# cpu_board.net
KiCad netlist of a schematic drawn in EAGLE
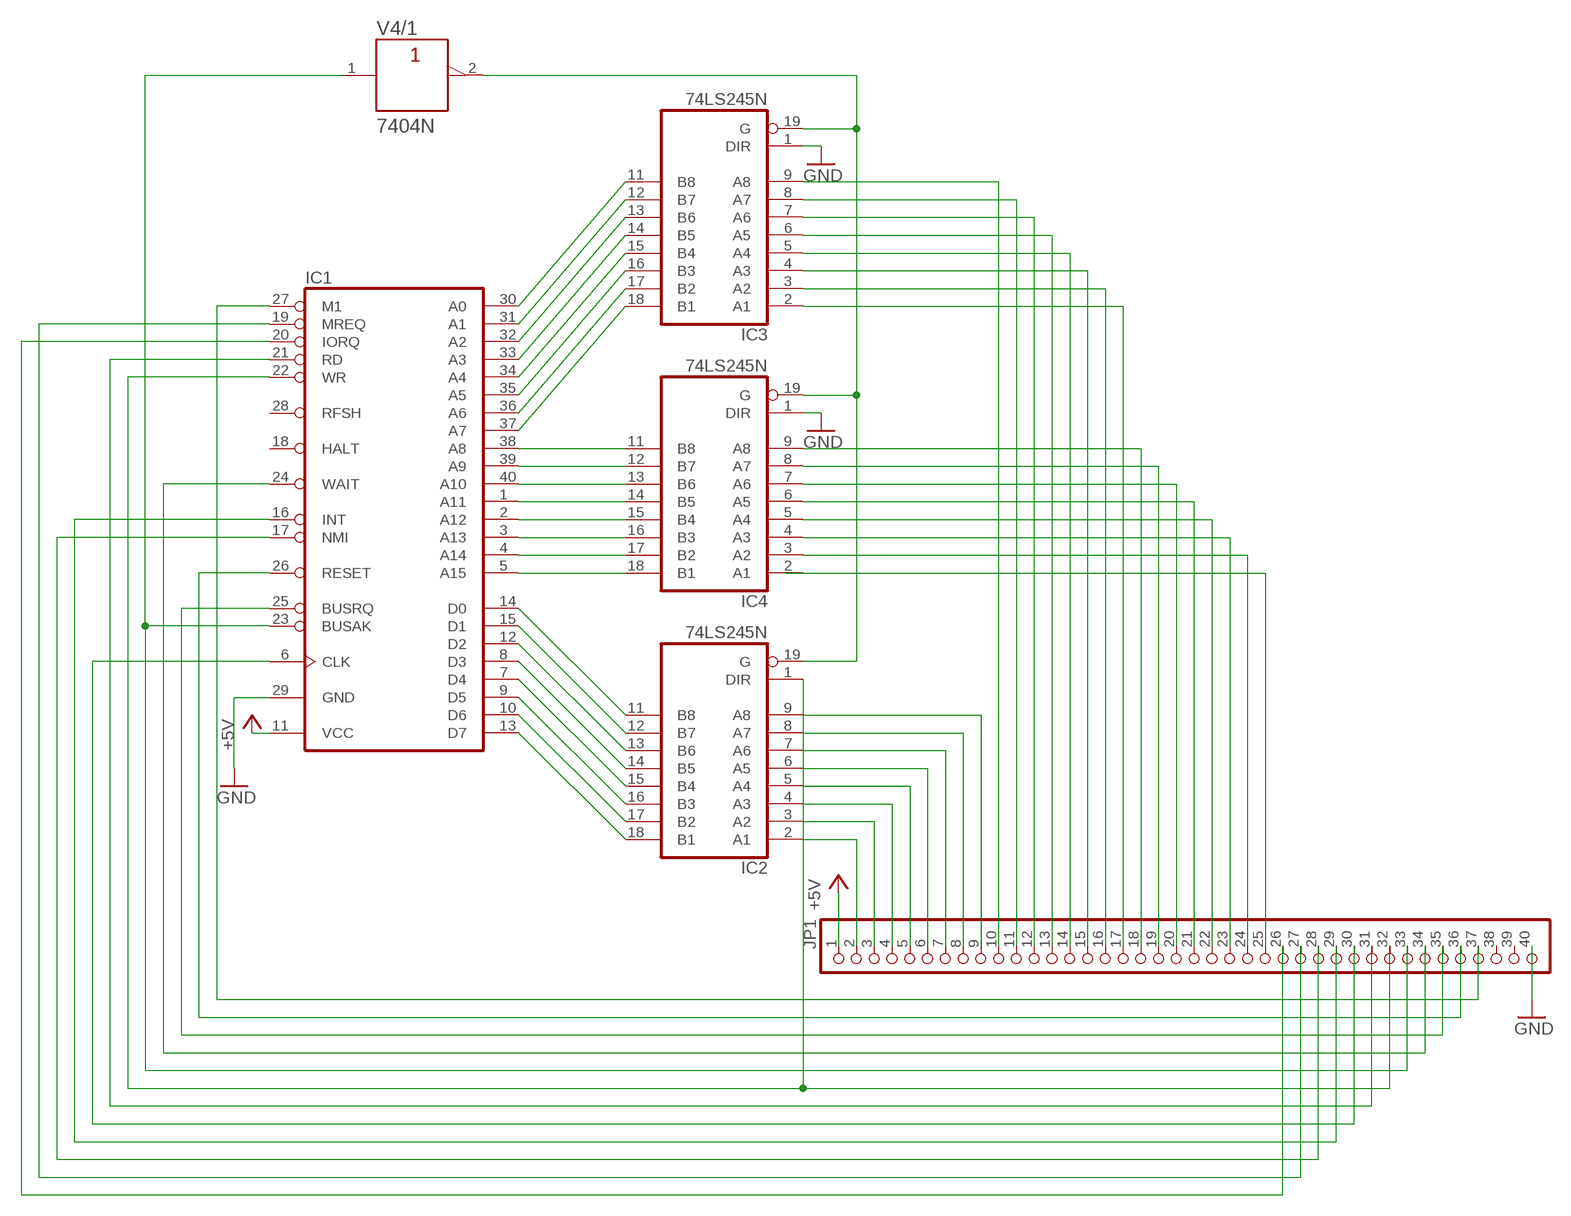
[diagram p0: schematic, sheet 1]

(export (version "E")
  (design (tool "Eeschema 10.0.6"))
  (components
    (comp (ref "IC1")
      (value "Z80CPU")
      (footprint "eagle-import:DIL40")
      (libsource (lib "eagle-import") (part "Z80CPU"))
    )
    (comp (ref "IC2")
      (value "74LS245N")
      (footprint "eagle-import:DIL20")
      (libsource (lib "eagle-import") (part "74245NLS"))
    )
    (comp (ref "IC3")
      (value "74LS245N")
      (footprint "eagle-import:DIL20")
      (libsource (lib "eagle-import") (part "74245NLS"))
    )
    (comp (ref "IC4")
      (value "74LS245N")
      (footprint "eagle-import:DIL20")
      (libsource (lib "eagle-import") (part "74245NLS"))
    )
    (comp (ref "JP1")
      (value "PINHD-1X40")
      (footprint "eagle-import:1X40")
      (libsource (lib "eagle-import") (part "PINHD-1X40"))
    )
    (comp (ref "V4")
      (value "7404N")
      (footprint "eagle-import:DIL14")
      (libsource (lib "eagle-import") (part "7404N"))
    )
  )
  (nets
    (net (code "1") (name "+5V") (class "Default")
      (node (ref "IC1") (pin "11") (pinfunction "VCC_11") (pintype "power_in"))
      (node (ref "JP1") (pin "1") (pinfunction "1_1") (pintype "passive"))
    )
    (net (code "2") (name "GND") (class "Default")
      (node (ref "IC1") (pin "29") (pinfunction "GND_29") (pintype "power_in"))
      (node (ref "IC3") (pin "1") (pinfunction "DIR_1") (pintype "input"))
      (node (ref "IC4") (pin "1") (pinfunction "DIR_1") (pintype "input"))
      (node (ref "JP1") (pin "40") (pinfunction "40_40") (pintype "passive"))
    )
    (net (code "3") (name "Net-(IC1-A0)") (class "Default")
      (node (ref "IC1") (pin "30") (pinfunction "A0_30") (pintype "output"))
      (node (ref "IC3") (pin "11") (pinfunction "B8_11") (pintype "bidirectional"))
    )
    (net (code "4") (name "Net-(IC1-A1)") (class "Default")
      (node (ref "IC1") (pin "31") (pinfunction "A1_31") (pintype "output"))
      (node (ref "IC3") (pin "12") (pinfunction "B7_12") (pintype "bidirectional"))
    )
    (net (code "5") (name "Net-(IC1-A2)") (class "Default")
      (node (ref "IC1") (pin "32") (pinfunction "A2_32") (pintype "output"))
      (node (ref "IC3") (pin "13") (pinfunction "B6_13") (pintype "bidirectional"))
    )
    (net (code "6") (name "Net-(IC1-A3)") (class "Default")
      (node (ref "IC1") (pin "33") (pinfunction "A3_33") (pintype "output"))
      (node (ref "IC3") (pin "14") (pinfunction "B5_14") (pintype "bidirectional"))
    )
    (net (code "7") (name "Net-(IC1-A4)") (class "Default")
      (node (ref "IC1") (pin "34") (pinfunction "A4_34") (pintype "output"))
      (node (ref "IC3") (pin "15") (pinfunction "B4_15") (pintype "bidirectional"))
    )
    (net (code "8") (name "Net-(IC1-A5)") (class "Default")
      (node (ref "IC1") (pin "35") (pinfunction "A5_35") (pintype "output"))
      (node (ref "IC3") (pin "16") (pinfunction "B3_16") (pintype "bidirectional"))
    )
    (net (code "9") (name "Net-(IC1-A6)") (class "Default")
      (node (ref "IC1") (pin "36") (pinfunction "A6_36") (pintype "output"))
      (node (ref "IC3") (pin "17") (pinfunction "B2_17") (pintype "bidirectional"))
    )
    (net (code "10") (name "Net-(IC1-A7)") (class "Default")
      (node (ref "IC1") (pin "37") (pinfunction "A7_37") (pintype "output"))
      (node (ref "IC3") (pin "18") (pinfunction "B1_18") (pintype "bidirectional"))
    )
    (net (code "11") (name "Net-(IC1-A8)") (class "Default")
      (node (ref "IC1") (pin "38") (pinfunction "A8_38") (pintype "output"))
      (node (ref "IC4") (pin "11") (pinfunction "B8_11") (pintype "bidirectional"))
    )
    (net (code "12") (name "Net-(IC1-A9)") (class "Default")
      (node (ref "IC1") (pin "39") (pinfunction "A9_39") (pintype "output"))
      (node (ref "IC4") (pin "12") (pinfunction "B7_12") (pintype "bidirectional"))
    )
    (net (code "13") (name "Net-(IC1-A10)") (class "Default")
      (node (ref "IC1") (pin "40") (pinfunction "A10_40") (pintype "output"))
      (node (ref "IC4") (pin "13") (pinfunction "B6_13") (pintype "bidirectional"))
    )
    (net (code "14") (name "Net-(IC1-A11)") (class "Default")
      (node (ref "IC1") (pin "1") (pinfunction "A11_1") (pintype "output"))
      (node (ref "IC4") (pin "14") (pinfunction "B5_14") (pintype "bidirectional"))
    )
    (net (code "15") (name "Net-(IC1-A12)") (class "Default")
      (node (ref "IC1") (pin "2") (pinfunction "A12_2") (pintype "output"))
      (node (ref "IC4") (pin "15") (pinfunction "B4_15") (pintype "bidirectional"))
    )
    (net (code "16") (name "Net-(IC1-A13)") (class "Default")
      (node (ref "IC1") (pin "3") (pinfunction "A13_3") (pintype "output"))
      (node (ref "IC4") (pin "16") (pinfunction "B3_16") (pintype "bidirectional"))
    )
    (net (code "17") (name "Net-(IC1-A14)") (class "Default")
      (node (ref "IC1") (pin "4") (pinfunction "A14_4") (pintype "output"))
      (node (ref "IC4") (pin "17") (pinfunction "B2_17") (pintype "bidirectional"))
    )
    (net (code "18") (name "Net-(IC1-A15)") (class "Default")
      (node (ref "IC1") (pin "5") (pinfunction "A15_5") (pintype "output"))
      (node (ref "IC4") (pin "18") (pinfunction "B1_18") (pintype "bidirectional"))
    )
    (net (code "19") (name "Net-(IC1-BUSAK)") (class "Default")
      (node (ref "IC1") (pin "23") (pinfunction "BUSAK_23") (pintype "output"))
      (node (ref "JP1") (pin "33") (pinfunction "33_33") (pintype "passive"))
      (node (ref "V4") (pin "1") (pinfunction "A_1") (pintype "input"))
    )
    (net (code "20") (name "Net-(IC1-BUSRQ)") (class "Default")
      (node (ref "IC1") (pin "25") (pinfunction "BUSRQ_25") (pintype "input"))
      (node (ref "JP1") (pin "35") (pinfunction "35_35") (pintype "passive"))
    )
    (net (code "21") (name "Net-(IC1-CLK)") (class "Default")
      (node (ref "IC1") (pin "6") (pinfunction "CLK_6") (pintype "input"))
      (node (ref "JP1") (pin "30") (pinfunction "30_30") (pintype "passive"))
    )
    (net (code "22") (name "Net-(IC1-D0)") (class "Default")
      (node (ref "IC1") (pin "14") (pinfunction "D0_14") (pintype "bidirectional"))
      (node (ref "IC2") (pin "11") (pinfunction "B8_11") (pintype "bidirectional"))
    )
    (net (code "23") (name "Net-(IC1-D1)") (class "Default")
      (node (ref "IC1") (pin "15") (pinfunction "D1_15") (pintype "bidirectional"))
      (node (ref "IC2") (pin "12") (pinfunction "B7_12") (pintype "bidirectional"))
    )
    (net (code "24") (name "Net-(IC1-D2)") (class "Default")
      (node (ref "IC1") (pin "12") (pinfunction "D2_12") (pintype "bidirectional"))
      (node (ref "IC2") (pin "13") (pinfunction "B6_13") (pintype "bidirectional"))
    )
    (net (code "25") (name "Net-(IC1-D3)") (class "Default")
      (node (ref "IC1") (pin "8") (pinfunction "D3_8") (pintype "bidirectional"))
      (node (ref "IC2") (pin "14") (pinfunction "B5_14") (pintype "bidirectional"))
    )
    (net (code "26") (name "Net-(IC1-D4)") (class "Default")
      (node (ref "IC1") (pin "7") (pinfunction "D4_7") (pintype "bidirectional"))
      (node (ref "IC2") (pin "15") (pinfunction "B4_15") (pintype "bidirectional"))
    )
    (net (code "27") (name "Net-(IC1-D5)") (class "Default")
      (node (ref "IC1") (pin "9") (pinfunction "D5_9") (pintype "bidirectional"))
      (node (ref "IC2") (pin "16") (pinfunction "B3_16") (pintype "bidirectional"))
    )
    (net (code "28") (name "Net-(IC1-D6)") (class "Default")
      (node (ref "IC1") (pin "10") (pinfunction "D6_10") (pintype "bidirectional"))
      (node (ref "IC2") (pin "17") (pinfunction "B2_17") (pintype "bidirectional"))
    )
    (net (code "29") (name "Net-(IC1-D7)") (class "Default")
      (node (ref "IC1") (pin "13") (pinfunction "D7_13") (pintype "bidirectional"))
      (node (ref "IC2") (pin "18") (pinfunction "B1_18") (pintype "bidirectional"))
    )
    (net (code "30") (name "Net-(IC1-INT)") (class "Default")
      (node (ref "IC1") (pin "16") (pinfunction "INT_16") (pintype "input"))
      (node (ref "JP1") (pin "29") (pinfunction "29_29") (pintype "passive"))
    )
    (net (code "31") (name "Net-(IC1-IORQ)") (class "Default")
      (node (ref "IC1") (pin "20") (pinfunction "IORQ_20") (pintype "output"))
      (node (ref "JP1") (pin "26") (pinfunction "26_26") (pintype "passive"))
    )
    (net (code "32") (name "Net-(IC1-M1)") (class "Default")
      (node (ref "IC1") (pin "27") (pinfunction "M1_27") (pintype "output"))
      (node (ref "JP1") (pin "37") (pinfunction "37_37") (pintype "passive"))
    )
    (net (code "33") (name "Net-(IC1-MREQ)") (class "Default")
      (node (ref "IC1") (pin "19") (pinfunction "MREQ_19") (pintype "output"))
      (node (ref "JP1") (pin "27") (pinfunction "27_27") (pintype "passive"))
    )
    (net (code "34") (name "Net-(IC1-NMI)") (class "Default")
      (node (ref "IC1") (pin "17") (pinfunction "NMI_17") (pintype "input"))
      (node (ref "JP1") (pin "28") (pinfunction "28_28") (pintype "passive"))
    )
    (net (code "35") (name "Net-(IC1-RD)") (class "Default")
      (node (ref "IC1") (pin "21") (pinfunction "RD_21") (pintype "output"))
      (node (ref "JP1") (pin "31") (pinfunction "31_31") (pintype "passive"))
    )
    (net (code "36") (name "Net-(IC1-RESET)") (class "Default")
      (node (ref "IC1") (pin "26") (pinfunction "RESET_26") (pintype "input"))
      (node (ref "JP1") (pin "36") (pinfunction "36_36") (pintype "passive"))
    )
    (net (code "37") (name "Net-(IC1-WAIT)") (class "Default")
      (node (ref "IC1") (pin "24") (pinfunction "WAIT_24") (pintype "input"))
      (node (ref "JP1") (pin "34") (pinfunction "34_34") (pintype "passive"))
    )
    (net (code "38") (name "Net-(IC1-WR)") (class "Default")
      (node (ref "IC1") (pin "22") (pinfunction "WR_22") (pintype "output"))
      (node (ref "IC2") (pin "1") (pinfunction "DIR_1") (pintype "input"))
      (node (ref "JP1") (pin "32") (pinfunction "32_32") (pintype "passive"))
    )
    (net (code "39") (name "Net-(IC2A-A1)") (class "Default")
      (node (ref "IC2") (pin "2") (pinfunction "A1_2") (pintype "bidirectional"))
      (node (ref "JP1") (pin "2") (pinfunction "2_2") (pintype "passive"))
    )
    (net (code "40") (name "Net-(IC2A-A2)") (class "Default")
      (node (ref "IC2") (pin "3") (pinfunction "A2_3") (pintype "bidirectional"))
      (node (ref "JP1") (pin "3") (pinfunction "3_3") (pintype "passive"))
    )
    (net (code "41") (name "Net-(IC2A-A3)") (class "Default")
      (node (ref "IC2") (pin "4") (pinfunction "A3_4") (pintype "bidirectional"))
      (node (ref "JP1") (pin "4") (pinfunction "4_4") (pintype "passive"))
    )
    (net (code "42") (name "Net-(IC2A-A4)") (class "Default")
      (node (ref "IC2") (pin "5") (pinfunction "A4_5") (pintype "bidirectional"))
      (node (ref "JP1") (pin "5") (pinfunction "5_5") (pintype "passive"))
    )
    (net (code "43") (name "Net-(IC2A-A5)") (class "Default")
      (node (ref "IC2") (pin "6") (pinfunction "A5_6") (pintype "bidirectional"))
      (node (ref "JP1") (pin "6") (pinfunction "6_6") (pintype "passive"))
    )
    (net (code "44") (name "Net-(IC2A-A6)") (class "Default")
      (node (ref "IC2") (pin "7") (pinfunction "A6_7") (pintype "bidirectional"))
      (node (ref "JP1") (pin "7") (pinfunction "7_7") (pintype "passive"))
    )
    (net (code "45") (name "Net-(IC2A-A7)") (class "Default")
      (node (ref "IC2") (pin "8") (pinfunction "A7_8") (pintype "bidirectional"))
      (node (ref "JP1") (pin "8") (pinfunction "8_8") (pintype "passive"))
    )
    (net (code "46") (name "Net-(IC2A-A8)") (class "Default")
      (node (ref "IC2") (pin "9") (pinfunction "A8_9") (pintype "bidirectional"))
      (node (ref "JP1") (pin "9") (pinfunction "9_9") (pintype "passive"))
    )
    (net (code "47") (name "Net-(IC2A-G)") (class "Default")
      (node (ref "IC2") (pin "19") (pinfunction "G_19") (pintype "input"))
      (node (ref "IC3") (pin "19") (pinfunction "G_19") (pintype "input"))
      (node (ref "IC4") (pin "19") (pinfunction "G_19") (pintype "input"))
      (node (ref "V4") (pin "2") (pinfunction "Y_2") (pintype "output"))
    )
    (net (code "48") (name "Net-(IC3A-A1)") (class "Default")
      (node (ref "IC3") (pin "2") (pinfunction "A1_2") (pintype "bidirectional"))
      (node (ref "JP1") (pin "17") (pinfunction "17_17") (pintype "passive"))
    )
    (net (code "49") (name "Net-(IC3A-A2)") (class "Default")
      (node (ref "IC3") (pin "3") (pinfunction "A2_3") (pintype "bidirectional"))
      (node (ref "JP1") (pin "16") (pinfunction "16_16") (pintype "passive"))
    )
    (net (code "50") (name "Net-(IC3A-A3)") (class "Default")
      (node (ref "IC3") (pin "4") (pinfunction "A3_4") (pintype "bidirectional"))
      (node (ref "JP1") (pin "15") (pinfunction "15_15") (pintype "passive"))
    )
    (net (code "51") (name "Net-(IC3A-A4)") (class "Default")
      (node (ref "IC3") (pin "5") (pinfunction "A4_5") (pintype "bidirectional"))
      (node (ref "JP1") (pin "14") (pinfunction "14_14") (pintype "passive"))
    )
    (net (code "52") (name "Net-(IC3A-A5)") (class "Default")
      (node (ref "IC3") (pin "6") (pinfunction "A5_6") (pintype "bidirectional"))
      (node (ref "JP1") (pin "13") (pinfunction "13_13") (pintype "passive"))
    )
    (net (code "53") (name "Net-(IC3A-A6)") (class "Default")
      (node (ref "IC3") (pin "7") (pinfunction "A6_7") (pintype "bidirectional"))
      (node (ref "JP1") (pin "12") (pinfunction "12_12") (pintype "passive"))
    )
    (net (code "54") (name "Net-(IC3A-A7)") (class "Default")
      (node (ref "IC3") (pin "8") (pinfunction "A7_8") (pintype "bidirectional"))
      (node (ref "JP1") (pin "11") (pinfunction "11_11") (pintype "passive"))
    )
    (net (code "55") (name "Net-(IC3A-A8)") (class "Default")
      (node (ref "IC3") (pin "9") (pinfunction "A8_9") (pintype "bidirectional"))
      (node (ref "JP1") (pin "10") (pinfunction "10_10") (pintype "passive"))
    )
    (net (code "56") (name "Net-(IC4A-A2)") (class "Default")
      (node (ref "IC4") (pin "3") (pinfunction "A2_3") (pintype "bidirectional"))
      (node (ref "JP1") (pin "24") (pinfunction "24_24") (pintype "passive"))
    )
    (net (code "57") (name "Net-(IC4A-A3)") (class "Default")
      (node (ref "IC4") (pin "4") (pinfunction "A3_4") (pintype "bidirectional"))
      (node (ref "JP1") (pin "23") (pinfunction "23_23") (pintype "passive"))
    )
    (net (code "58") (name "Net-(IC4A-A4)") (class "Default")
      (node (ref "IC4") (pin "5") (pinfunction "A4_5") (pintype "bidirectional"))
      (node (ref "JP1") (pin "22") (pinfunction "22_22") (pintype "passive"))
    )
    (net (code "59") (name "Net-(IC4A-A5)") (class "Default")
      (node (ref "IC4") (pin "6") (pinfunction "A5_6") (pintype "bidirectional"))
      (node (ref "JP1") (pin "21") (pinfunction "21_21") (pintype "passive"))
    )
    (net (code "60") (name "Net-(IC4A-A6)") (class "Default")
      (node (ref "IC4") (pin "7") (pinfunction "A6_7") (pintype "bidirectional"))
      (node (ref "JP1") (pin "20") (pinfunction "20_20") (pintype "passive"))
    )
    (net (code "61") (name "Net-(IC4A-A7)") (class "Default")
      (node (ref "IC4") (pin "8") (pinfunction "A7_8") (pintype "bidirectional"))
      (node (ref "JP1") (pin "19") (pinfunction "19_19") (pintype "passive"))
    )
    (net (code "62") (name "Net-(IC4A-A8)") (class "Default")
      (node (ref "IC4") (pin "9") (pinfunction "A8_9") (pintype "bidirectional"))
      (node (ref "JP1") (pin "18") (pinfunction "18_18") (pintype "passive"))
    )
    (net (code "63") (name "unconnected-(IC1-HALT-Pad18)") (class "Default")
      (node (ref "IC1") (pin "18") (pinfunction "HALT_18") (pintype "output"))
    )
    (net (code "64") (name "unconnected-(IC1-RFSH-Pad28)") (class "Default")
      (node (ref "IC1") (pin "28") (pinfunction "RFSH_28") (pintype "output"))
    )
    (net (code "65") (name "unconnected-(IC4A-A1-Pad2)") (class "Default")
      (node (ref "IC4") (pin "2") (pinfunction "A1_2") (pintype "bidirectional"))
    )
    (net (code "66") (name "unconnected-(JP1-Pad25)") (class "Default")
      (node (ref "JP1") (pin "25") (pinfunction "25_25") (pintype "passive"))
    )
    (net (code "67") (name "unconnected-(JP1-Pad38)") (class "Default")
      (node (ref "JP1") (pin "38") (pinfunction "38_38") (pintype "passive"))
    )
    (net (code "68") (name "unconnected-(JP1-Pad39)") (class "Default")
      (node (ref "JP1") (pin "39") (pinfunction "39_39") (pintype "passive"))
    )
  )
)
